# Rx.net
KiCad netlist of a schematic drawn in EAGLE
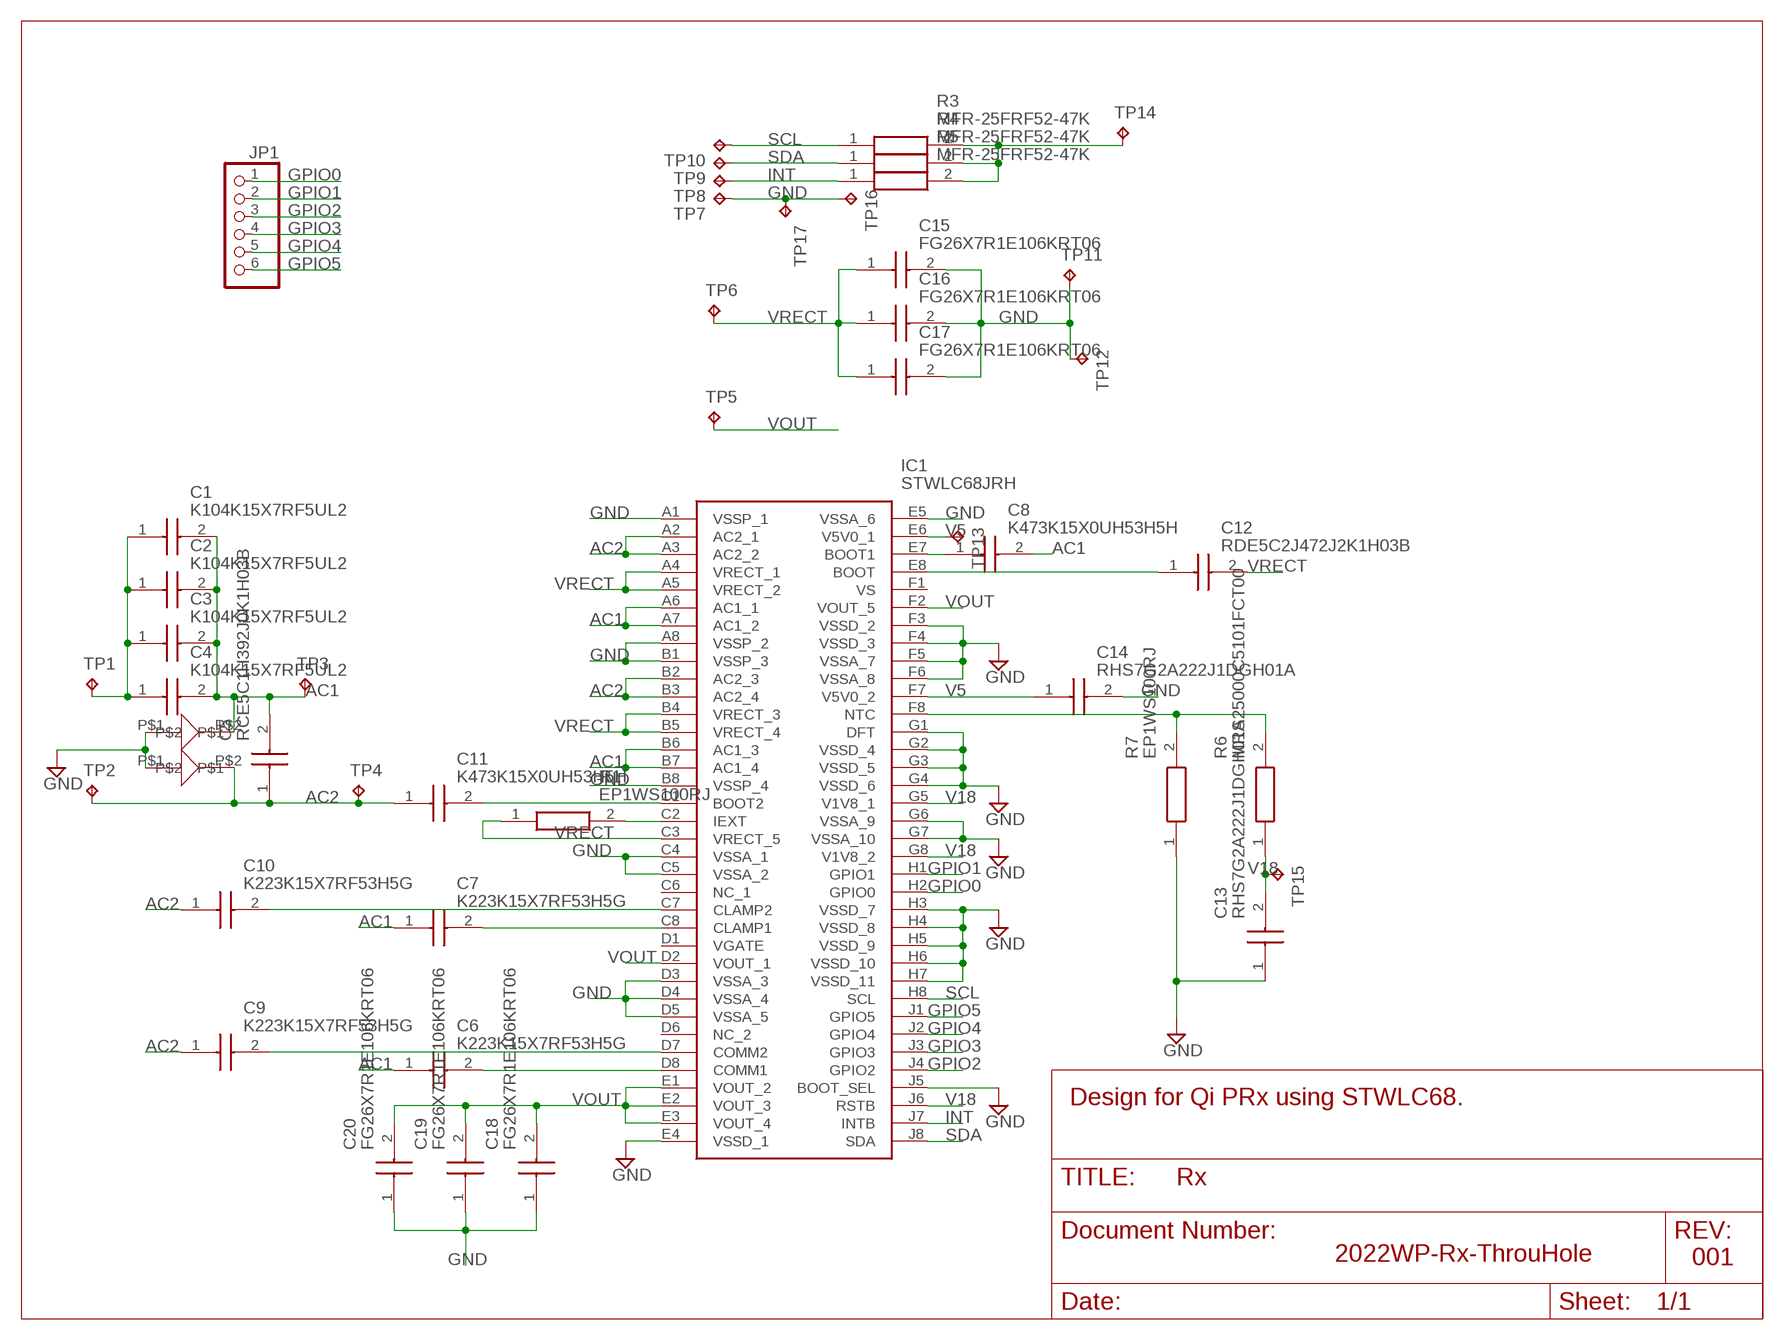
[diagram p0: schematic, sheet 1]

(export (version "E")
  (design (tool "Eeschema 10.0.6"))
  (components
    (comp (ref "C1")
      (value "K104K15X7RF5UL2")
      (footprint "eagle-import:K104K15X7RF5UL2")
      (fields (field (name "MOUSER_PART_NUMBER") "594-K104K15X7RF5UL2"))
      (libsource (lib "eagle-import") (part "K104K15X7RF5UL2"))
    )
    (comp (ref "C2")
      (value "K104K15X7RF5UL2")
      (footprint "eagle-import:K104K15X7RF5UL2")
      (fields (field (name "MOUSER_PART_NUMBER") "594-K104K15X7RF5UL2"))
      (libsource (lib "eagle-import") (part "K104K15X7RF5UL2"))
    )
    (comp (ref "C3")
      (value "K104K15X7RF5UL2")
      (footprint "eagle-import:K104K15X7RF5UL2")
      (fields (field (name "MOUSER_PART_NUMBER") "594-K104K15X7RF5UL2"))
      (libsource (lib "eagle-import") (part "K104K15X7RF5UL2"))
    )
    (comp (ref "C4")
      (value "K104K15X7RF5UL2")
      (footprint "eagle-import:K104K15X7RF5UL2")
      (fields (field (name "MOUSER_PART_NUMBER") "594-K104K15X7RF5UL2"))
      (libsource (lib "eagle-import") (part "K104K15X7RF5UL2"))
    )
    (comp (ref "C5")
      (value "RCE5C1H392J0K1H03B")
      (footprint "eagle-import:RCER71H104K0K1H03B")
      (libsource (lib "eagle-import") (part "RCE5C1H392J0K1H03B"))
    )
    (comp (ref "C6")
      (value "K223K15X7RF53H5G")
      (footprint "eagle-import:K223K15X7RF53H5G")
      (fields (field (name "MOUSER_PART_NUMBER") "594-K223K15X7RF53H5G"))
      (libsource (lib "eagle-import") (part "K223K15X7RF53H5G"))
    )
    (comp (ref "C7")
      (value "K223K15X7RF53H5G")
      (footprint "eagle-import:K223K15X7RF53H5G")
      (fields (field (name "MOUSER_PART_NUMBER") "594-K223K15X7RF53H5G"))
      (libsource (lib "eagle-import") (part "K223K15X7RF53H5G"))
    )
    (comp (ref "C8")
      (value "K473K15X0UH53H5H")
      (footprint "eagle-import:K473K15X0UH53H5H")
      (fields (field (name "MOUSER_PART_NUMBER") "594-K473K15X0UH53H5H"))
      (libsource (lib "eagle-import") (part "K473K15X0UH53H5H"))
    )
    (comp (ref "C9")
      (value "K223K15X7RF53H5G")
      (footprint "eagle-import:K223K15X7RF53H5G")
      (fields (field (name "MOUSER_PART_NUMBER") "594-K223K15X7RF53H5G"))
      (libsource (lib "eagle-import") (part "K223K15X7RF53H5G"))
    )
    (comp (ref "C10")
      (value "K223K15X7RF53H5G")
      (footprint "eagle-import:K223K15X7RF53H5G")
      (fields (field (name "MOUSER_PART_NUMBER") "594-K223K15X7RF53H5G"))
      (libsource (lib "eagle-import") (part "K223K15X7RF53H5G"))
    )
    (comp (ref "C11")
      (value "K473K15X0UH53H5H")
      (footprint "eagle-import:K473K15X0UH53H5H")
      (fields (field (name "MOUSER_PART_NUMBER") "594-K473K15X0UH53H5H"))
      (libsource (lib "eagle-import") (part "K473K15X0UH53H5H"))
    )
    (comp (ref "C12")
      (value "RDE5C2J472J2K1H03B")
      (footprint "eagle-import:RCE5C1H104J2A2H03B")
      (fields (field (name "MOUSER_PART_NUMBER") "81-RDE5C2J472J2K1H3B"))
      (libsource (lib "eagle-import") (part "RDE5C2J472J2K1H03B"))
    )
    (comp (ref "C13")
      (value "RHS7G2A222J1DGH01A")
      (footprint "eagle-import:RHS7G2A182J1A2H01B")
      (fields (field (name "MOUSER_PART_NUMBER") "81-RHS7G2A222J1DGH1A"))
      (libsource (lib "eagle-import") (part "RHS7G2A222J1DGH01A"))
    )
    (comp (ref "C14")
      (value "RHS7G2A222J1DGH01A")
      (footprint "eagle-import:RHS7G2A182J1A2H01B")
      (fields (field (name "MOUSER_PART_NUMBER") "81-RHS7G2A222J1DGH1A"))
      (libsource (lib "eagle-import") (part "RHS7G2A222J1DGH01A"))
    )
    (comp (ref "C15")
      (value "FG26X7R1E106KRT06")
      (footprint "eagle-import:FG26")
      (fields (field (name "MOUSER_PART_NUMBER") "810-FG26X7R1E106KRT6"))
      (libsource (lib "eagle-import") (part "FG26X7R1E106KRT06"))
    )
    (comp (ref "C16")
      (value "FG26X7R1E106KRT06")
      (footprint "eagle-import:FG26")
      (fields (field (name "MOUSER_PART_NUMBER") "810-FG26X7R1E106KRT6"))
      (libsource (lib "eagle-import") (part "FG26X7R1E106KRT06"))
    )
    (comp (ref "C17")
      (value "FG26X7R1E106KRT06")
      (footprint "eagle-import:FG26")
      (fields (field (name "MOUSER_PART_NUMBER") "810-FG26X7R1E106KRT6"))
      (libsource (lib "eagle-import") (part "FG26X7R1E106KRT06"))
    )
    (comp (ref "C18")
      (value "FG26X7R1E106KRT06")
      (footprint "eagle-import:FG26")
      (fields (field (name "MOUSER_PART_NUMBER") "810-FG26X7R1E106KRT6"))
      (libsource (lib "eagle-import") (part "FG26X7R1E106KRT06"))
    )
    (comp (ref "C19")
      (value "FG26X7R1E106KRT06")
      (footprint "eagle-import:FG26")
      (fields (field (name "MOUSER_PART_NUMBER") "810-FG26X7R1E106KRT6"))
      (libsource (lib "eagle-import") (part "FG26X7R1E106KRT06"))
    )
    (comp (ref "C20")
      (value "FG26X7R1E106KRT06")
      (footprint "eagle-import:FG26")
      (fields (field (name "MOUSER_PART_NUMBER") "810-FG26X7R1E106KRT6"))
      (libsource (lib "eagle-import") (part "FG26X7R1E106KRT06"))
    )
    (comp (ref "IC1")
      (value "STWLC68JRH")
      (footprint "eagle-import:BGA72C40P9X9_441X376X58")
      (fields (field (name "MOUSER_PART_NUMBER") "511-STWLC68JRH"))
      (libsource (lib "eagle-import") (part "STWLC68JRH"))
    )
    (comp (ref "JP1")
      (value "PINHD-1X6")
      (footprint "eagle-import:1X06")
      (libsource (lib "eagle-import") (part "PINHD-1X6"))
    )
    (comp (ref "R1")
      (value "EP1WS100RJ")
      (footprint "eagle-import:RESAD2400W54L1000D350")
      (fields (field (name "MOUSER_PART_NUMBER") "279-EP1WS100RJ"))
      (libsource (lib "eagle-import") (part "EP1WS100RJ"))
    )
    (comp (ref "R3")
      (value "MFR-25FRF52-47K")
      (footprint "eagle-import:RESAD1590W60L630D240")
      (fields (field (name "MOUSER_PART_NUMBER") "603-MFR-25FRF52-47K"))
      (libsource (lib "eagle-import") (part "MFR-25FRF52-47K"))
    )
    (comp (ref "R4")
      (value "MFR-25FRF52-47K")
      (footprint "eagle-import:RESAD1590W60L630D240")
      (fields (field (name "MOUSER_PART_NUMBER") "603-MFR-25FRF52-47K"))
      (libsource (lib "eagle-import") (part "MFR-25FRF52-47K"))
    )
    (comp (ref "R5")
      (value "MFR-25FRF52-47K")
      (footprint "eagle-import:RESAD1590W60L630D240")
      (fields (field (name "MOUSER_PART_NUMBER") "603-MFR-25FRF52-47K"))
      (libsource (lib "eagle-import") (part "MFR-25FRF52-47K"))
    )
    (comp (ref "R6")
      (value "MRS25000C5101FCT00")
      (footprint "eagle-import:RESAD1650W60L650D250")
      (fields (field (name "MOUSER_PART_NUMBER") "594-MRS25000C5101FCT"))
      (libsource (lib "eagle-import") (part "MRS25000C5101FCT00"))
    )
    (comp (ref "R7")
      (value "EP1WS100RJ")
      (footprint "eagle-import:RESAD2400W54L1000D350")
      (fields (field (name "MOUSER_PART_NUMBER") "279-EP1WS100RJ"))
      (libsource (lib "eagle-import") (part "EP1WS100RJ"))
    )
    (comp (ref "TP1")
      (value "TPPAD1-13")
      (footprint "eagle-import:P1-13")
      (libsource (lib "eagle-import") (part "TPPAD1-13"))
    )
    (comp (ref "TP2")
      (value "TPPAD1-13")
      (footprint "eagle-import:P1-13")
      (libsource (lib "eagle-import") (part "TPPAD1-13"))
    )
    (comp (ref "TP3")
      (value "TPPAD1-13")
      (footprint "eagle-import:P1-13")
      (libsource (lib "eagle-import") (part "TPPAD1-13"))
    )
    (comp (ref "TP4")
      (value "TPPAD1-13")
      (footprint "eagle-import:P1-13")
      (libsource (lib "eagle-import") (part "TPPAD1-13"))
    )
    (comp (ref "TP5")
      (value "TPPAD1-13")
      (footprint "eagle-import:P1-13")
      (libsource (lib "eagle-import") (part "TPPAD1-13"))
    )
    (comp (ref "TP6")
      (value "TPPAD1-13")
      (footprint "eagle-import:P1-13")
      (libsource (lib "eagle-import") (part "TPPAD1-13"))
    )
    (comp (ref "TP7")
      (value "TPPAD1-13")
      (footprint "eagle-import:P1-13")
      (libsource (lib "eagle-import") (part "TPPAD1-13"))
    )
    (comp (ref "TP8")
      (value "TPPAD1-13")
      (footprint "eagle-import:P1-13")
      (libsource (lib "eagle-import") (part "TPPAD1-13"))
    )
    (comp (ref "TP9")
      (value "TPPAD1-13")
      (footprint "eagle-import:P1-13")
      (libsource (lib "eagle-import") (part "TPPAD1-13"))
    )
    (comp (ref "TP10")
      (value "TPPAD1-13")
      (footprint "eagle-import:P1-13")
      (libsource (lib "eagle-import") (part "TPPAD1-13"))
    )
    (comp (ref "TP11")
      (value "TPPAD1-13")
      (footprint "eagle-import:P1-13")
      (libsource (lib "eagle-import") (part "TPPAD1-13"))
    )
    (comp (ref "TP12")
      (value "TPPAD1-13")
      (footprint "eagle-import:P1-13")
      (libsource (lib "eagle-import") (part "TPPAD1-13"))
    )
    (comp (ref "TP13")
      (value "TPPAD1-13")
      (footprint "eagle-import:P1-13")
      (libsource (lib "eagle-import") (part "TPPAD1-13"))
    )
    (comp (ref "TP14")
      (value "TPPAD1-13")
      (footprint "eagle-import:P1-13")
      (libsource (lib "eagle-import") (part "TPPAD1-13"))
    )
    (comp (ref "TP15")
      (value "TPPAD1-13")
      (footprint "eagle-import:P1-13")
      (libsource (lib "eagle-import") (part "TPPAD1-13"))
    )
    (comp (ref "TP16")
      (value "TPPAD1-13")
      (footprint "eagle-import:P1-13")
      (libsource (lib "eagle-import") (part "TPPAD1-13"))
    )
    (comp (ref "TP17")
      (value "TPPAD1-13")
      (footprint "eagle-import:P1-13")
      (libsource (lib "eagle-import") (part "TPPAD1-13"))
    )
    (comp (ref "U$1")
      (value "SA16A-E3/54")
      (footprint "eagle-import:SA16A-E3_54")
      (libsource (lib "eagle-import") (part "SA16A-E3/54"))
    )
    (comp (ref "U$2")
      (value "SA16A-E3/54")
      (footprint "eagle-import:SA16A-E3_54")
      (libsource (lib "eagle-import") (part "SA16A-E3/54"))
    )
  )
  (nets
    (net (code "1") (name "/AC1") (class "Default")
      (node (ref "C1") (pin "2") (pinfunction "2_2") (pintype "bidirectional"))
      (node (ref "C2") (pin "2") (pinfunction "2_2") (pintype "bidirectional"))
      (node (ref "C3") (pin "2") (pinfunction "2_2") (pintype "bidirectional"))
      (node (ref "C4") (pin "2") (pinfunction "2_2") (pintype "bidirectional"))
      (node (ref "C5") (pin "2") (pinfunction "2_2") (pintype "bidirectional"))
      (node (ref "C6") (pin "1") (pinfunction "1_1") (pintype "bidirectional"))
      (node (ref "C7") (pin "1") (pinfunction "1_1") (pintype "bidirectional"))
      (node (ref "C8") (pin "2") (pinfunction "2_2") (pintype "bidirectional"))
      (node (ref "IC1") (pin "A6") (pinfunction "AC1_1_A6") (pintype "bidirectional"))
      (node (ref "IC1") (pin "A7") (pinfunction "AC1_2_A7") (pintype "bidirectional"))
      (node (ref "IC1") (pin "B6") (pinfunction "AC1_3_B6") (pintype "bidirectional"))
      (node (ref "IC1") (pin "B7") (pinfunction "AC1_4_B7") (pintype "bidirectional"))
      (node (ref "TP3") (pin "TP") (pinfunction "TP_TP") (pintype "input"))
      (node (ref "U$1") (pin "P$2") (pinfunction "P$2_P$2") (pintype "bidirectional"))
    )
    (net (code "2") (name "/AC2") (class "Default")
      (node (ref "C10") (pin "1") (pinfunction "1_1") (pintype "bidirectional"))
      (node (ref "C11") (pin "1") (pinfunction "1_1") (pintype "bidirectional"))
      (node (ref "C5") (pin "1") (pinfunction "1_1") (pintype "bidirectional"))
      (node (ref "C9") (pin "1") (pinfunction "1_1") (pintype "bidirectional"))
      (node (ref "IC1") (pin "A2") (pinfunction "AC2_1_A2") (pintype "bidirectional"))
      (node (ref "IC1") (pin "A3") (pinfunction "AC2_2_A3") (pintype "bidirectional"))
      (node (ref "IC1") (pin "B2") (pinfunction "AC2_3_B2") (pintype "bidirectional"))
      (node (ref "IC1") (pin "B3") (pinfunction "AC2_4_B3") (pintype "bidirectional"))
      (node (ref "TP2") (pin "TP") (pinfunction "TP_TP") (pintype "input"))
      (node (ref "TP4") (pin "TP") (pinfunction "TP_TP") (pintype "input"))
      (node (ref "U$2") (pin "P$2") (pinfunction "P$2_P$2") (pintype "bidirectional"))
    )
    (net (code "3") (name "/GPIO0") (class "Default")
      (node (ref "IC1") (pin "H2") (pinfunction "GPIO0_H2") (pintype "bidirectional"))
      (node (ref "JP1") (pin "1") (pinfunction "1_1") (pintype "passive"))
    )
    (net (code "4") (name "/GPIO1") (class "Default")
      (node (ref "IC1") (pin "H1") (pinfunction "GPIO1_H1") (pintype "bidirectional"))
      (node (ref "JP1") (pin "2") (pinfunction "2_2") (pintype "passive"))
    )
    (net (code "5") (name "/GPIO2") (class "Default")
      (node (ref "IC1") (pin "J4") (pinfunction "GPIO2_J4") (pintype "bidirectional"))
      (node (ref "JP1") (pin "3") (pinfunction "3_3") (pintype "passive"))
    )
    (net (code "6") (name "/GPIO3") (class "Default")
      (node (ref "IC1") (pin "J3") (pinfunction "GPIO3_J3") (pintype "bidirectional"))
      (node (ref "JP1") (pin "4") (pinfunction "4_4") (pintype "passive"))
    )
    (net (code "7") (name "/GPIO4") (class "Default")
      (node (ref "IC1") (pin "J2") (pinfunction "GPIO4_J2") (pintype "bidirectional"))
      (node (ref "JP1") (pin "5") (pinfunction "5_5") (pintype "passive"))
    )
    (net (code "8") (name "/GPIO5") (class "Default")
      (node (ref "IC1") (pin "J1") (pinfunction "GPIO5_J1") (pintype "bidirectional"))
      (node (ref "JP1") (pin "6") (pinfunction "6_6") (pintype "passive"))
    )
    (net (code "9") (name "/INT") (class "Default")
      (node (ref "IC1") (pin "J7") (pinfunction "INTB_J7") (pintype "bidirectional"))
      (node (ref "R5") (pin "1") (pinfunction "1_1") (pintype "bidirectional"))
      (node (ref "TP8") (pin "TP") (pinfunction "TP_TP") (pintype "input"))
    )
    (net (code "10") (name "/SCL") (class "Default")
      (node (ref "IC1") (pin "H8") (pinfunction "SCL_H8") (pintype "bidirectional"))
      (node (ref "R3") (pin "1") (pinfunction "1_1") (pintype "bidirectional"))
      (node (ref "TP10") (pin "TP") (pinfunction "TP_TP") (pintype "input"))
    )
    (net (code "11") (name "/SDA") (class "Default")
      (node (ref "IC1") (pin "J8") (pinfunction "SDA_J8") (pintype "bidirectional"))
      (node (ref "R4") (pin "1") (pinfunction "1_1") (pintype "bidirectional"))
      (node (ref "TP9") (pin "TP") (pinfunction "TP_TP") (pintype "input"))
    )
    (net (code "12") (name "/V5") (class "Default")
      (node (ref "C14") (pin "1") (pinfunction "1_1") (pintype "bidirectional"))
      (node (ref "IC1") (pin "E6") (pinfunction "V5V0_1_E6") (pintype "bidirectional"))
      (node (ref "IC1") (pin "F7") (pinfunction "V5V0_2_F7") (pintype "bidirectional"))
      (node (ref "TP13") (pin "TP") (pinfunction "TP_TP") (pintype "input"))
    )
    (net (code "13") (name "/V18") (class "Default")
      (node (ref "C13") (pin "2") (pinfunction "2_2") (pintype "bidirectional"))
      (node (ref "IC1") (pin "G5") (pinfunction "V1V8_1_G5") (pintype "bidirectional"))
      (node (ref "IC1") (pin "G8") (pinfunction "V1V8_2_G8") (pintype "bidirectional"))
      (node (ref "IC1") (pin "J6") (pinfunction "RSTB_J6") (pintype "bidirectional"))
      (node (ref "R6") (pin "1") (pinfunction "1_1") (pintype "bidirectional"))
      (node (ref "TP15") (pin "TP") (pinfunction "TP_TP") (pintype "input"))
    )
    (net (code "14") (name "/VOUT") (class "Default")
      (node (ref "C18") (pin "2") (pinfunction "2_2") (pintype "bidirectional"))
      (node (ref "C19") (pin "2") (pinfunction "2_2") (pintype "bidirectional"))
      (node (ref "C20") (pin "2") (pinfunction "2_2") (pintype "bidirectional"))
      (node (ref "IC1") (pin "D2") (pinfunction "VOUT_1_D2") (pintype "bidirectional"))
      (node (ref "IC1") (pin "E1") (pinfunction "VOUT_2_E1") (pintype "bidirectional"))
      (node (ref "IC1") (pin "E2") (pinfunction "VOUT_3_E2") (pintype "bidirectional"))
      (node (ref "IC1") (pin "E3") (pinfunction "VOUT_4_E3") (pintype "bidirectional"))
      (node (ref "IC1") (pin "F2") (pinfunction "VOUT_5_F2") (pintype "bidirectional"))
      (node (ref "TP5") (pin "TP") (pinfunction "TP_TP") (pintype "input"))
    )
    (net (code "15") (name "/VRECT") (class "Default")
      (node (ref "C12") (pin "2") (pinfunction "2_2") (pintype "bidirectional"))
      (node (ref "C15") (pin "1") (pinfunction "1_1") (pintype "bidirectional"))
      (node (ref "C16") (pin "1") (pinfunction "1_1") (pintype "bidirectional"))
      (node (ref "C17") (pin "1") (pinfunction "1_1") (pintype "bidirectional"))
      (node (ref "IC1") (pin "A4") (pinfunction "VRECT_1_A4") (pintype "bidirectional"))
      (node (ref "IC1") (pin "A5") (pinfunction "VRECT_2_A5") (pintype "bidirectional"))
      (node (ref "IC1") (pin "B4") (pinfunction "VRECT_3_B4") (pintype "bidirectional"))
      (node (ref "IC1") (pin "B5") (pinfunction "VRECT_4_B5") (pintype "bidirectional"))
      (node (ref "IC1") (pin "C3") (pinfunction "VRECT_5_C3") (pintype "bidirectional"))
      (node (ref "R1") (pin "1") (pinfunction "1_1") (pintype "bidirectional"))
      (node (ref "TP6") (pin "TP") (pinfunction "TP_TP") (pintype "input"))
    )
    (net (code "16") (name "GND") (class "Default")
      (node (ref "C13") (pin "1") (pinfunction "1_1") (pintype "bidirectional"))
      (node (ref "C14") (pin "2") (pinfunction "2_2") (pintype "bidirectional"))
      (node (ref "C15") (pin "2") (pinfunction "2_2") (pintype "bidirectional"))
      (node (ref "C16") (pin "2") (pinfunction "2_2") (pintype "bidirectional"))
      (node (ref "C17") (pin "2") (pinfunction "2_2") (pintype "bidirectional"))
      (node (ref "C18") (pin "1") (pinfunction "1_1") (pintype "bidirectional"))
      (node (ref "C19") (pin "1") (pinfunction "1_1") (pintype "bidirectional"))
      (node (ref "C20") (pin "1") (pinfunction "1_1") (pintype "bidirectional"))
      (node (ref "IC1") (pin "A1") (pinfunction "VSSP_1_A1") (pintype "bidirectional"))
      (node (ref "IC1") (pin "A8") (pinfunction "VSSP_2_A8") (pintype "bidirectional"))
      (node (ref "IC1") (pin "B1") (pinfunction "VSSP_3_B1") (pintype "bidirectional"))
      (node (ref "IC1") (pin "B8") (pinfunction "VSSP_4_B8") (pintype "bidirectional"))
      (node (ref "IC1") (pin "C4") (pinfunction "VSSA_1_C4") (pintype "bidirectional"))
      (node (ref "IC1") (pin "C5") (pinfunction "VSSA_2_C5") (pintype "bidirectional"))
      (node (ref "IC1") (pin "D3") (pinfunction "VSSA_3_D3") (pintype "bidirectional"))
      (node (ref "IC1") (pin "D4") (pinfunction "VSSA_4_D4") (pintype "bidirectional"))
      (node (ref "IC1") (pin "D5") (pinfunction "VSSA_5_D5") (pintype "bidirectional"))
      (node (ref "IC1") (pin "E4") (pinfunction "VSSD_1_E4") (pintype "bidirectional"))
      (node (ref "IC1") (pin "E5") (pinfunction "VSSA_6_E5") (pintype "bidirectional"))
      (node (ref "IC1") (pin "F3") (pinfunction "VSSD_2_F3") (pintype "bidirectional"))
      (node (ref "IC1") (pin "F4") (pinfunction "VSSD_3_F4") (pintype "bidirectional"))
      (node (ref "IC1") (pin "F5") (pinfunction "VSSA_7_F5") (pintype "bidirectional"))
      (node (ref "IC1") (pin "F6") (pinfunction "VSSA_8_F6") (pintype "bidirectional"))
      (node (ref "IC1") (pin "G1") (pinfunction "DFT_G1") (pintype "bidirectional"))
      (node (ref "IC1") (pin "G2") (pinfunction "VSSD_4_G2") (pintype "bidirectional"))
      (node (ref "IC1") (pin "G3") (pinfunction "VSSD_5_G3") (pintype "bidirectional"))
      (node (ref "IC1") (pin "G4") (pinfunction "VSSD_6_G4") (pintype "bidirectional"))
      (node (ref "IC1") (pin "G6") (pinfunction "VSSA_9_G6") (pintype "bidirectional"))
      (node (ref "IC1") (pin "G7") (pinfunction "VSSA_10_G7") (pintype "bidirectional"))
      (node (ref "IC1") (pin "H3") (pinfunction "VSSD_7_H3") (pintype "bidirectional"))
      (node (ref "IC1") (pin "H4") (pinfunction "VSSD_8_H4") (pintype "bidirectional"))
      (node (ref "IC1") (pin "H5") (pinfunction "VSSD_9_H5") (pintype "bidirectional"))
      (node (ref "IC1") (pin "H6") (pinfunction "VSSD_10_H6") (pintype "bidirectional"))
      (node (ref "IC1") (pin "H7") (pinfunction "VSSD_11_H7") (pintype "bidirectional"))
      (node (ref "IC1") (pin "J5") (pinfunction "BOOT_SEL_J5") (pintype "bidirectional"))
      (node (ref "R7") (pin "1") (pinfunction "1_1") (pintype "bidirectional"))
      (node (ref "TP11") (pin "TP") (pinfunction "TP_TP") (pintype "input"))
      (node (ref "TP12") (pin "TP") (pinfunction "TP_TP") (pintype "input"))
      (node (ref "TP16") (pin "TP") (pinfunction "TP_TP") (pintype "input"))
      (node (ref "TP17") (pin "TP") (pinfunction "TP_TP") (pintype "input"))
      (node (ref "TP7") (pin "TP") (pinfunction "TP_TP") (pintype "input"))
      (node (ref "U$1") (pin "P$1") (pinfunction "P$1_P$1") (pintype "bidirectional"))
      (node (ref "U$2") (pin "P$1") (pinfunction "P$1_P$1") (pintype "bidirectional"))
    )
    (net (code "17") (name "Net-(C1-Pad1)") (class "Default")
      (node (ref "C1") (pin "1") (pinfunction "1_1") (pintype "bidirectional"))
      (node (ref "C2") (pin "1") (pinfunction "1_1") (pintype "bidirectional"))
      (node (ref "C3") (pin "1") (pinfunction "1_1") (pintype "bidirectional"))
      (node (ref "C4") (pin "1") (pinfunction "1_1") (pintype "bidirectional"))
      (node (ref "TP1") (pin "TP") (pinfunction "TP_TP") (pintype "input"))
    )
    (net (code "18") (name "Net-(IC1-BOOT)") (class "Default")
      (node (ref "C12") (pin "1") (pinfunction "1_1") (pintype "bidirectional"))
      (node (ref "IC1") (pin "E8") (pinfunction "BOOT_E8") (pintype "bidirectional"))
    )
    (net (code "19") (name "Net-(IC1-BOOT1)") (class "Default")
      (node (ref "C8") (pin "1") (pinfunction "1_1") (pintype "bidirectional"))
      (node (ref "IC1") (pin "E7") (pinfunction "BOOT1_E7") (pintype "bidirectional"))
    )
    (net (code "20") (name "Net-(IC1-BOOT2)") (class "Default")
      (node (ref "C11") (pin "2") (pinfunction "2_2") (pintype "bidirectional"))
      (node (ref "IC1") (pin "C1") (pinfunction "BOOT2_C1") (pintype "bidirectional"))
    )
    (net (code "21") (name "Net-(IC1-CLAMP1)") (class "Default")
      (node (ref "C7") (pin "2") (pinfunction "2_2") (pintype "bidirectional"))
      (node (ref "IC1") (pin "C8") (pinfunction "CLAMP1_C8") (pintype "bidirectional"))
    )
    (net (code "22") (name "Net-(IC1-CLAMP2)") (class "Default")
      (node (ref "C10") (pin "2") (pinfunction "2_2") (pintype "bidirectional"))
      (node (ref "IC1") (pin "C7") (pinfunction "CLAMP2_C7") (pintype "bidirectional"))
    )
    (net (code "23") (name "Net-(IC1-COMM1)") (class "Default")
      (node (ref "C6") (pin "2") (pinfunction "2_2") (pintype "bidirectional"))
      (node (ref "IC1") (pin "D8") (pinfunction "COMM1_D8") (pintype "bidirectional"))
    )
    (net (code "24") (name "Net-(IC1-COMM2)") (class "Default")
      (node (ref "C9") (pin "2") (pinfunction "2_2") (pintype "bidirectional"))
      (node (ref "IC1") (pin "D7") (pinfunction "COMM2_D7") (pintype "bidirectional"))
    )
    (net (code "25") (name "Net-(IC1-IEXT)") (class "Default")
      (node (ref "IC1") (pin "C2") (pinfunction "IEXT_C2") (pintype "bidirectional"))
      (node (ref "R1") (pin "2") (pinfunction "2_2") (pintype "bidirectional"))
    )
    (net (code "26") (name "Net-(IC1-NTC)") (class "Default")
      (node (ref "IC1") (pin "F8") (pinfunction "NTC_F8") (pintype "bidirectional"))
      (node (ref "R6") (pin "2") (pinfunction "2_2") (pintype "bidirectional"))
      (node (ref "R7") (pin "2") (pinfunction "2_2") (pintype "bidirectional"))
    )
    (net (code "27") (name "Net-(R3-Pad2)") (class "Default")
      (node (ref "R3") (pin "2") (pinfunction "2_2") (pintype "bidirectional"))
      (node (ref "R4") (pin "2") (pinfunction "2_2") (pintype "bidirectional"))
      (node (ref "R5") (pin "2") (pinfunction "2_2") (pintype "bidirectional"))
      (node (ref "TP14") (pin "TP") (pinfunction "TP_TP") (pintype "input"))
    )
    (net (code "28") (name "unconnected-(IC1-NC_1-PadC6)") (class "Default")
      (node (ref "IC1") (pin "C6") (pinfunction "NC_1_C6") (pintype "bidirectional"))
    )
    (net (code "29") (name "unconnected-(IC1-NC_2-PadD6)") (class "Default")
      (node (ref "IC1") (pin "D6") (pinfunction "NC_2_D6") (pintype "bidirectional"))
    )
    (net (code "30") (name "unconnected-(IC1-VGATE-PadD1)") (class "Default")
      (node (ref "IC1") (pin "D1") (pinfunction "VGATE_D1") (pintype "bidirectional"))
    )
    (net (code "31") (name "unconnected-(IC1-VS-PadF1)") (class "Default")
      (node (ref "IC1") (pin "F1") (pinfunction "VS_F1") (pintype "bidirectional"))
    )
  )
)
